# Puzzle-loudness_sensor.net
KiCad netlist of a schematic drawn in EAGLE
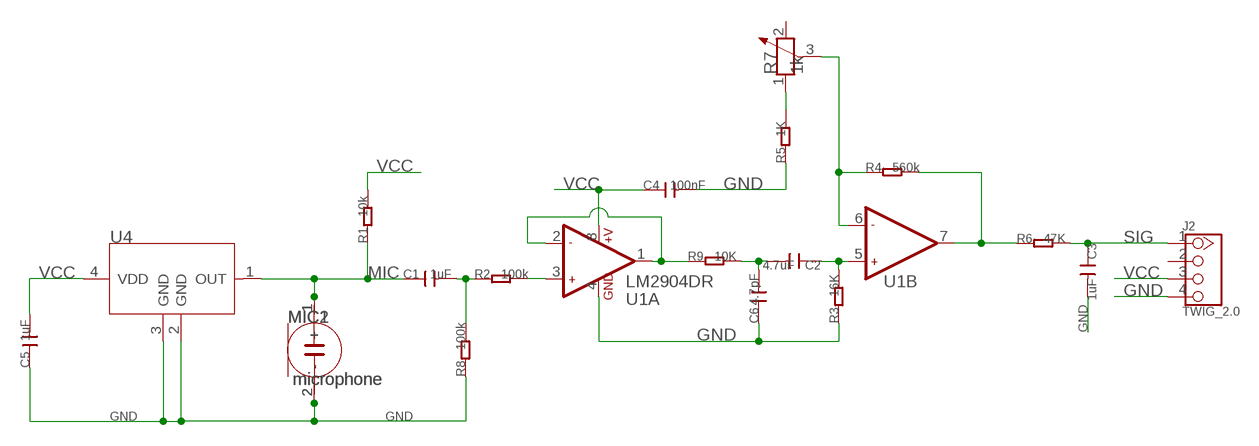
[diagram p0: schematic, sheet 1]

(export (version "E")
  (design (tool "Eeschema 10.0.6"))
  (components
    (comp (ref "C1")
      (value "1uF")
      (footprint "eagle-import:C0603")
      (libsource (lib "eagle-import") (part "C-0603"))
    )
    (comp (ref "C2")
      (value "4.7uF")
      (footprint "eagle-import:C0805")
      (libsource (lib "eagle-import") (part "C-0805"))
    )
    (comp (ref "C3")
      (value "1uF")
      (footprint "eagle-import:C0603")
      (libsource (lib "eagle-import") (part "C-0603"))
    )
    (comp (ref "C4")
      (value "100nF")
      (footprint "eagle-import:C0603")
      (libsource (lib "eagle-import") (part "C-0603"))
    )
    (comp (ref "C5")
      (value "1uF")
      (footprint "eagle-import:C0603")
      (libsource (lib "eagle-import") (part "C-0603"))
    )
    (comp (ref "C6")
      (value "4.7pF")
      (footprint "eagle-import:C0603")
      (libsource (lib "eagle-import") (part "C-0603"))
    )
    (comp (ref "J2")
      (value "TWIG_2.0")
      (footprint "eagle-import:2.0_1X4")
      (libsource (lib "eagle-import") (part "TWIG_2.0"))
    )
    (comp (ref "MIC1")
      (value "microphone")
      (footprint "eagle-import:2P-D8.9MM")
      (libsource (lib "eagle-import") (part "MICROPHONE"))
    )
    (comp (ref "MIC2")
      (value "microphone")
      (footprint "eagle-import:2P-D8.9MM")
      (libsource (lib "eagle-import") (part "MICROPHONE"))
    )
    (comp (ref "R1")
      (value "10k")
      (footprint "eagle-import:R0603")
      (libsource (lib "eagle-import") (part "R-0603"))
    )
    (comp (ref "R2")
      (value "100k")
      (footprint "eagle-import:R0603")
      (libsource (lib "eagle-import") (part "R-0603"))
    )
    (comp (ref "R3")
      (value "16K")
      (footprint "eagle-import:R0603")
      (libsource (lib "eagle-import") (part "R-0603"))
    )
    (comp (ref "R4")
      (value "560k")
      (footprint "eagle-import:R0603")
      (libsource (lib "eagle-import") (part "R-0603"))
    )
    (comp (ref "R5")
      (value "1K")
      (footprint "eagle-import:R0603")
      (libsource (lib "eagle-import") (part "R-0603"))
    )
    (comp (ref "R6")
      (value "47K")
      (footprint "eagle-import:R0603")
      (libsource (lib "eagle-import") (part "R-0603"))
    )
    (comp (ref "R7")
      (value "1k")
      (footprint "eagle-import:3P-SQUA-7X6.8")
      (libsource (lib "eagle-import") (part "R-POTENTIOMETER'3362'"))
    )
    (comp (ref "R8")
      (value "100k")
      (footprint "eagle-import:R0603")
      (libsource (lib "eagle-import") (part "R-0603"))
    )
    (comp (ref "R9")
      (value "10K")
      (footprint "eagle-import:R0603")
      (libsource (lib "eagle-import") (part "R-0603"))
    )
    (comp (ref "U1")
      (value "LM2904DR")
      (footprint "eagle-import:SO08")
      (libsource (lib "eagle-import") (part "LMV358D"))
    )
    (comp (ref "U4")
      (value "SENSOR-MULPS4CX")
      (footprint "eagle-import:4P-SMD-2.95X3.76X1.1H")
      (libsource (lib "eagle-import") (part "SENSOR-MULPS4CX"))
    )
  )
  (nets
    (net (code "1") (name "/GND") (class "Default")
      (node (ref "C3") (pin "2") (pinfunction "2_2") (pintype "passive"))
      (node (ref "C4") (pin "2") (pinfunction "2_2") (pintype "passive"))
      (node (ref "C5") (pin "1") (pinfunction "1_1") (pintype "passive"))
      (node (ref "C6") (pin "1") (pinfunction "1_1") (pintype "passive"))
      (node (ref "J2") (pin "4") (pinfunction "4_4") (pintype "bidirectional"))
      (node (ref "MIC1") (pin "2") (pinfunction "-_2") (pintype "bidirectional"))
      (node (ref "MIC2") (pin "2") (pinfunction "-_2") (pintype "bidirectional"))
      (node (ref "R3") (pin "1") (pinfunction "1_1") (pintype "passive"))
      (node (ref "R5") (pin "1") (pinfunction "1_1") (pintype "passive"))
      (node (ref "R8") (pin "1") (pinfunction "1_1") (pintype "passive"))
      (node (ref "U1") (pin "4") (pinfunction "GND_4") (pintype "power_in"))
      (node (ref "U4") (pin "2") (pinfunction "GND_2") (pintype "bidirectional"))
      (node (ref "U4") (pin "3") (pinfunction "GND_3") (pintype "bidirectional"))
    )
    (net (code "2") (name "/MIC") (class "Default")
      (node (ref "C1") (pin "1") (pinfunction "1_1") (pintype "passive"))
      (node (ref "MIC1") (pin "1") (pinfunction "+_1") (pintype "bidirectional"))
      (node (ref "MIC2") (pin "1") (pinfunction "+_1") (pintype "bidirectional"))
      (node (ref "R1") (pin "1") (pinfunction "1_1") (pintype "passive"))
      (node (ref "U4") (pin "1") (pinfunction "OUT_1") (pintype "bidirectional"))
    )
    (net (code "3") (name "/SIG") (class "Default")
      (node (ref "C3") (pin "1") (pinfunction "1_1") (pintype "passive"))
      (node (ref "J2") (pin "1") (pinfunction "1_1") (pintype "bidirectional"))
      (node (ref "R6") (pin "2") (pinfunction "2_2") (pintype "passive"))
    )
    (net (code "4") (name "/VCC") (class "Default")
      (node (ref "C4") (pin "1") (pinfunction "1_1") (pintype "passive"))
      (node (ref "C5") (pin "2") (pinfunction "2_2") (pintype "passive"))
      (node (ref "J2") (pin "3") (pinfunction "3_3") (pintype "bidirectional"))
      (node (ref "R1") (pin "2") (pinfunction "2_2") (pintype "passive"))
      (node (ref "U1") (pin "8") (pinfunction "+V_8") (pintype "power_in"))
      (node (ref "U4") (pin "4") (pinfunction "VDD_4") (pintype "bidirectional"))
    )
    (net (code "5") (name "Net-(C1-Pad2)") (class "Default")
      (node (ref "C1") (pin "2") (pinfunction "2_2") (pintype "passive"))
      (node (ref "R2") (pin "1") (pinfunction "1_1") (pintype "passive"))
      (node (ref "R8") (pin "2") (pinfunction "2_2") (pintype "passive"))
    )
    (net (code "6") (name "Net-(C2-Pad2)") (class "Default")
      (node (ref "C2") (pin "2") (pinfunction "2_2") (pintype "passive"))
      (node (ref "C6") (pin "2") (pinfunction "2_2") (pintype "passive"))
      (node (ref "R9") (pin "2") (pinfunction "2_2") (pintype "passive"))
    )
    (net (code "7") (name "Net-(R5-Pad2)") (class "Default")
      (node (ref "R5") (pin "2") (pinfunction "2_2") (pintype "passive"))
      (node (ref "R7") (pin "1") (pinfunction "1_1") (pintype "passive"))
    )
    (net (code "8") (name "Net-(U1A-+IN1)") (class "Default")
      (node (ref "R2") (pin "2") (pinfunction "2_2") (pintype "passive"))
      (node (ref "U1") (pin "3") (pinfunction "+IN1_3") (pintype "input"))
    )
    (net (code "9") (name "Net-(U1A--IN1)") (class "Default")
      (node (ref "R9") (pin "1") (pinfunction "1_1") (pintype "passive"))
      (node (ref "U1") (pin "1") (pinfunction "OUT1_1") (pintype "output"))
      (node (ref "U1") (pin "2") (pinfunction "-IN1_2") (pintype "input"))
    )
    (net (code "10") (name "Net-(U1B-+IN2)") (class "Default")
      (node (ref "C2") (pin "1") (pinfunction "1_1") (pintype "passive"))
      (node (ref "R3") (pin "2") (pinfunction "2_2") (pintype "passive"))
      (node (ref "U1") (pin "5") (pinfunction "+IN2_5") (pintype "input"))
    )
    (net (code "11") (name "Net-(U1B--IN2)") (class "Default")
      (node (ref "R4") (pin "1") (pinfunction "1_1") (pintype "passive"))
      (node (ref "R7") (pin "3") (pinfunction "3_3") (pintype "passive"))
      (node (ref "U1") (pin "6") (pinfunction "-IN2_6") (pintype "input"))
    )
    (net (code "12") (name "Net-(U1B-OUT2)") (class "Default")
      (node (ref "R4") (pin "2") (pinfunction "2_2") (pintype "passive"))
      (node (ref "R6") (pin "1") (pinfunction "1_1") (pintype "passive"))
      (node (ref "U1") (pin "7") (pinfunction "OUT2_7") (pintype "output"))
    )
    (net (code "13") (name "unconnected-(J2-Pad2)") (class "Default")
      (node (ref "J2") (pin "2") (pinfunction "2_2") (pintype "bidirectional"))
    )
    (net (code "14") (name "unconnected-(R7-Pad2)") (class "Default")
      (node (ref "R7") (pin "2") (pinfunction "2_2") (pintype "passive"))
    )
  )
)
